# v1_0_3_2026-06-08.net
KiCad netlist of a schematic drawn in EasyEDA Pro
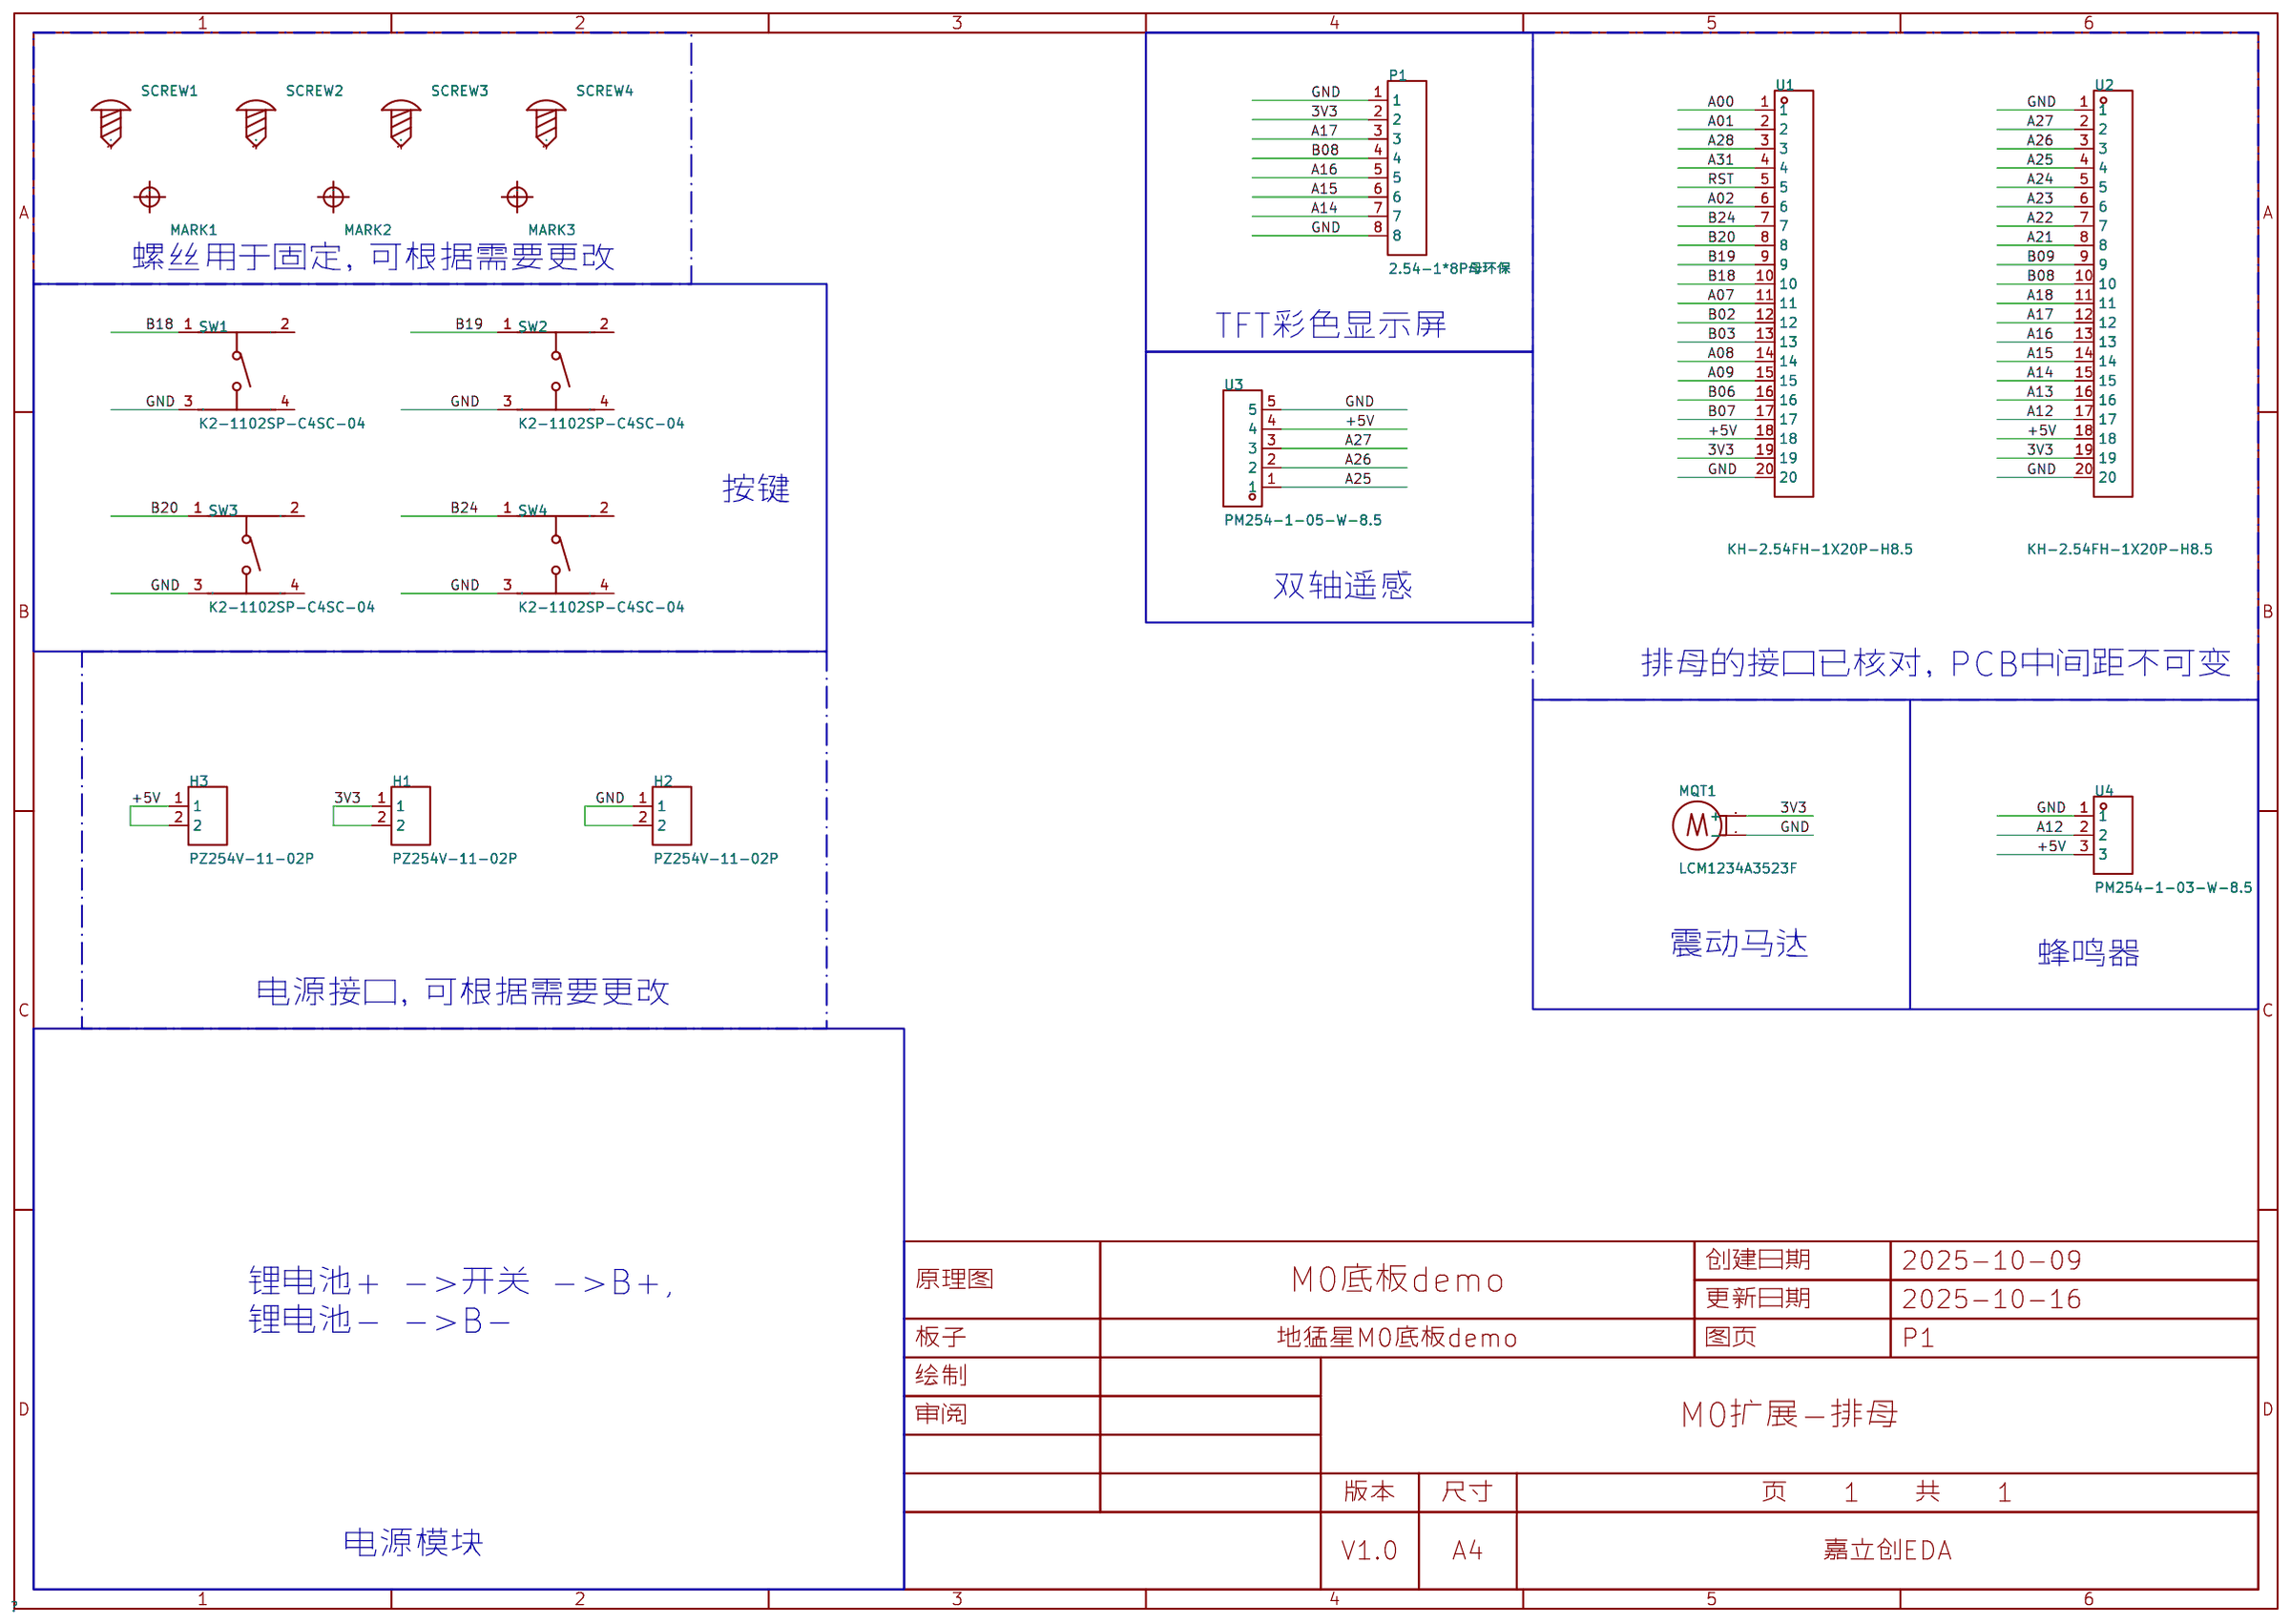
[diagram p0: schematic sheet]

(export (version "E")
  (design (tool "Eeschema 10.0.6"))
  (components
    (comp (ref "H1")
      (value "PZ254V-11-02P")
      (footprint "easyedapro:HDR-TH_2P-P2.54-V-M")
      (fields (field (name "Manufacturer") "XFCN(兴飞)"))
      (libsource (lib "easyedapro") (part "PZ254V-11-02P"))
    )
    (comp (ref "H2")
      (value "PZ254V-11-02P")
      (footprint "easyedapro:HDR-TH_2P-P2.54-V-M")
      (fields (field (name "Manufacturer") "XFCN(兴飞)"))
      (libsource (lib "easyedapro") (part "PZ254V-11-02P"))
    )
    (comp (ref "H3")
      (value "PZ254V-11-02P")
      (footprint "easyedapro:HDR-TH_2P-P2.54-V-M")
      (fields (field (name "Manufacturer") "XFCN(兴飞)"))
      (libsource (lib "easyedapro") (part "PZ254V-11-02P"))
    )
    (comp (ref "MARK1")
      (value "~")
      (footprint "easyedapro:Mark-Point-1mm")
      (libsource (lib "easyedapro") (part "Mark-Point"))
    )
    (comp (ref "MARK2")
      (value "~")
      (footprint "easyedapro:Mark-Point-1mm")
      (libsource (lib "easyedapro") (part "Mark-Point"))
    )
    (comp (ref "MARK3")
      (value "~")
      (footprint "easyedapro:Mark-Point-1mm")
      (libsource (lib "easyedapro") (part "Mark-Point"))
    )
    (comp (ref "MQT1")
      (value "LCM1234A3523F")
      (footprint "easyedapro:VIBRATING-MOTOR-SMD_WELDING")
      (fields (field (name "Manufacturer") "LEADER(立得)"))
      (libsource (lib "easyedapro") (part "LCM1234A3523F"))
    )
    (comp (ref "P1")
      (value "2.54-1*8P母环保")
      (footprint "easyedapro:HDR-TH_8P-P2.54-V-F")
      (fields (field (name "Manufacturer") "BOOMELE(博穆精密)"))
      (libsource (lib "easyedapro") (part "Header-Female-2.54_1x8"))
    )
    (comp (ref "SCREW1")
      (value "~")
      (footprint "easyedapro:M3螺丝")
      (libsource (lib "easyedapro") (part "螺丝孔"))
    )
    (comp (ref "SCREW2")
      (value "~")
      (footprint "easyedapro:M3螺丝")
      (libsource (lib "easyedapro") (part "螺丝孔"))
    )
    (comp (ref "SCREW3")
      (value "~")
      (footprint "easyedapro:M3螺丝")
      (libsource (lib "easyedapro") (part "螺丝孔"))
    )
    (comp (ref "SCREW4")
      (value "~")
      (footprint "easyedapro:M3螺丝")
      (libsource (lib "easyedapro") (part "螺丝孔"))
    )
    (comp (ref "SW1")
      (value "K2-1102SP-C4SC-04")
      (footprint "easyedapro:KEY-SMD_4P-L6.0-W6.0-P4.50-LS9.5-BL")
      (description "电路结构:单刀单掷;按钮形状:圆形按钮;作用力:2.5N;安装方式:立贴;开关长度:6mm;开关宽度:6mm;开关高度:5mm;触点电流:50mA;额定电压:12V;带灯:-;工作寿命:10万次;")
      (fields (field (name "Manufacturer") "韩国韩荣"))
      (libsource (lib "easyedapro") (part "K2-1102SP-C4SC-04"))
    )
    (comp (ref "SW2")
      (value "K2-1102SP-C4SC-04")
      (footprint "easyedapro:KEY-SMD_4P-L6.0-W6.0-P4.50-LS9.5-BL")
      (description "电路结构:单刀单掷;按钮形状:圆形按钮;作用力:2.5N;安装方式:立贴;开关长度:6mm;开关宽度:6mm;开关高度:5mm;触点电流:50mA;额定电压:12V;带灯:-;工作寿命:10万次;")
      (fields (field (name "Manufacturer") "韩国韩荣"))
      (libsource (lib "easyedapro") (part "K2-1102SP-C4SC-04"))
    )
    (comp (ref "SW3")
      (value "K2-1102SP-C4SC-04")
      (footprint "easyedapro:KEY-SMD_4P-L6.0-W6.0-P4.50-LS9.5-BL")
      (description "电路结构:单刀单掷;按钮形状:圆形按钮;作用力:2.5N;安装方式:立贴;开关长度:6mm;开关宽度:6mm;开关高度:5mm;触点电流:50mA;额定电压:12V;带灯:-;工作寿命:10万次;")
      (fields (field (name "Manufacturer") "韩国韩荣"))
      (libsource (lib "easyedapro") (part "K2-1102SP-C4SC-04"))
    )
    (comp (ref "SW4")
      (value "K2-1102SP-C4SC-04")
      (footprint "easyedapro:KEY-SMD_4P-L6.0-W6.0-P4.50-LS9.5-BL")
      (description "电路结构:单刀单掷;按钮形状:圆形按钮;作用力:2.5N;安装方式:立贴;开关长度:6mm;开关宽度:6mm;开关高度:5mm;触点电流:50mA;额定电压:12V;带灯:-;工作寿命:10万次;")
      (fields (field (name "Manufacturer") "韩国韩荣"))
      (libsource (lib "easyedapro") (part "K2-1102SP-C4SC-04"))
    )
    (comp (ref "U1")
      (value "KH-2.54FH-1X20P-H8.5")
      (footprint "easyedapro:HDR-TH_20P-P2.54-V-F-2")
      (fields (field (name "Manufacturer") "kinghelm(金航标)"))
      (libsource (lib "easyedapro") (part "KH-2.54FH-1X20P-H8.5"))
    )
    (comp (ref "U2")
      (value "KH-2.54FH-1X20P-H8.5")
      (footprint "easyedapro:HDR-TH_20P-P2.54-V-F-2")
      (fields (field (name "Manufacturer") "kinghelm(金航标)"))
      (libsource (lib "easyedapro") (part "KH-2.54FH-1X20P-H8.5"))
    )
    (comp (ref "U3")
      (value "PM254-1-05-W-8.5")
      (footprint "easyedapro:HDR-TH_5P-P2.54-H-F-W10.0-N")
      (fields (field (name "Manufacturer") "HCTL(华灿天禄)"))
      (libsource (lib "easyedapro") (part "PM254-1-05-W-8.5"))
    )
    (comp (ref "U4")
      (value "PM254-1-03-W-8.5")
      (footprint "easyedapro:HDR-TH_3P-P2.54-H-F-W10.0-N")
      (fields (field (name "Manufacturer") "HCTL(华灿天禄)"))
      (libsource (lib "easyedapro") (part "PM254-1-03-W-8.5"))
    )
  )
  (nets
    (net (code "1") (name "/+5V") (class "Default")
      (node (ref "H3") (pin "1") (pinfunction "1_1") (pintype "unspecified"))
      (node (ref "H3") (pin "2") (pinfunction "2_2") (pintype "unspecified"))
      (node (ref "U1") (pin "18") (pinfunction "18_18") (pintype "unspecified"))
      (node (ref "U2") (pin "18") (pinfunction "18_18") (pintype "unspecified"))
      (node (ref "U3") (pin "4") (pinfunction "4_4") (pintype "unspecified"))
      (node (ref "U4") (pin "3") (pinfunction "3_3") (pintype "unspecified"))
    )
    (net (code "2") (name "/3V3") (class "Default")
      (node (ref "H1") (pin "1") (pinfunction "1_1") (pintype "unspecified"))
      (node (ref "H1") (pin "2") (pinfunction "2_2") (pintype "unspecified"))
      (node (ref "MQT1") (pin "2") (pinfunction "+_2") (pintype "unspecified"))
      (node (ref "P1") (pin "2") (pinfunction "2_2") (pintype "unspecified"))
      (node (ref "U1") (pin "19") (pinfunction "19_19") (pintype "unspecified"))
      (node (ref "U2") (pin "19") (pinfunction "19_19") (pintype "unspecified"))
    )
    (net (code "3") (name "/A00") (class "Default")
      (node (ref "U1") (pin "1") (pinfunction "1_1") (pintype "unspecified"))
    )
    (net (code "4") (name "/A01") (class "Default")
      (node (ref "U1") (pin "2") (pinfunction "2_2") (pintype "unspecified"))
    )
    (net (code "5") (name "/A02") (class "Default")
      (node (ref "U1") (pin "6") (pinfunction "6_6") (pintype "unspecified"))
    )
    (net (code "6") (name "/A07") (class "Default")
      (node (ref "U1") (pin "11") (pinfunction "11_11") (pintype "unspecified"))
    )
    (net (code "7") (name "/A08") (class "Default")
      (node (ref "U1") (pin "14") (pinfunction "14_14") (pintype "unspecified"))
    )
    (net (code "8") (name "/A09") (class "Default")
      (node (ref "U1") (pin "15") (pinfunction "15_15") (pintype "unspecified"))
    )
    (net (code "9") (name "/A12") (class "Default")
      (node (ref "U2") (pin "17") (pinfunction "17_17") (pintype "unspecified"))
      (node (ref "U4") (pin "2") (pinfunction "2_2") (pintype "unspecified"))
    )
    (net (code "10") (name "/A13") (class "Default")
      (node (ref "U2") (pin "16") (pinfunction "16_16") (pintype "unspecified"))
    )
    (net (code "11") (name "/A14") (class "Default")
      (node (ref "P1") (pin "7") (pinfunction "7_7") (pintype "unspecified"))
      (node (ref "U2") (pin "15") (pinfunction "15_15") (pintype "unspecified"))
    )
    (net (code "12") (name "/A15") (class "Default")
      (node (ref "P1") (pin "6") (pinfunction "6_6") (pintype "unspecified"))
      (node (ref "U2") (pin "14") (pinfunction "14_14") (pintype "unspecified"))
    )
    (net (code "13") (name "/A16") (class "Default")
      (node (ref "P1") (pin "5") (pinfunction "5_5") (pintype "unspecified"))
      (node (ref "U2") (pin "13") (pinfunction "13_13") (pintype "unspecified"))
    )
    (net (code "14") (name "/A17") (class "Default")
      (node (ref "P1") (pin "3") (pinfunction "3_3") (pintype "unspecified"))
      (node (ref "U2") (pin "12") (pinfunction "12_12") (pintype "unspecified"))
    )
    (net (code "15") (name "/A18") (class "Default")
      (node (ref "U2") (pin "11") (pinfunction "11_11") (pintype "unspecified"))
    )
    (net (code "16") (name "/A21") (class "Default")
      (node (ref "U2") (pin "8") (pinfunction "8_8") (pintype "unspecified"))
    )
    (net (code "17") (name "/A22") (class "Default")
      (node (ref "U2") (pin "7") (pinfunction "7_7") (pintype "unspecified"))
    )
    (net (code "18") (name "/A23") (class "Default")
      (node (ref "U2") (pin "6") (pinfunction "6_6") (pintype "unspecified"))
    )
    (net (code "19") (name "/A24") (class "Default")
      (node (ref "U2") (pin "5") (pinfunction "5_5") (pintype "unspecified"))
    )
    (net (code "20") (name "/A25") (class "Default")
      (node (ref "U2") (pin "4") (pinfunction "4_4") (pintype "unspecified"))
      (node (ref "U3") (pin "1") (pinfunction "1_1") (pintype "unspecified"))
    )
    (net (code "21") (name "/A26") (class "Default")
      (node (ref "U2") (pin "3") (pinfunction "3_3") (pintype "unspecified"))
      (node (ref "U3") (pin "2") (pinfunction "2_2") (pintype "unspecified"))
    )
    (net (code "22") (name "/A27") (class "Default")
      (node (ref "U2") (pin "2") (pinfunction "2_2") (pintype "unspecified"))
      (node (ref "U3") (pin "3") (pinfunction "3_3") (pintype "unspecified"))
    )
    (net (code "23") (name "/A28") (class "Default")
      (node (ref "U1") (pin "3") (pinfunction "3_3") (pintype "unspecified"))
    )
    (net (code "24") (name "/A31") (class "Default")
      (node (ref "U1") (pin "4") (pinfunction "4_4") (pintype "unspecified"))
    )
    (net (code "25") (name "/B02") (class "Default")
      (node (ref "U1") (pin "12") (pinfunction "12_12") (pintype "unspecified"))
    )
    (net (code "26") (name "/B03") (class "Default")
      (node (ref "U1") (pin "13") (pinfunction "13_13") (pintype "unspecified"))
    )
    (net (code "27") (name "/B06") (class "Default")
      (node (ref "U1") (pin "16") (pinfunction "16_16") (pintype "unspecified"))
    )
    (net (code "28") (name "/B07") (class "Default")
      (node (ref "U1") (pin "17") (pinfunction "17_17") (pintype "unspecified"))
    )
    (net (code "29") (name "/B08") (class "Default")
      (node (ref "P1") (pin "4") (pinfunction "4_4") (pintype "unspecified"))
      (node (ref "U2") (pin "10") (pinfunction "10_10") (pintype "unspecified"))
    )
    (net (code "30") (name "/B09") (class "Default")
      (node (ref "U2") (pin "9") (pinfunction "9_9") (pintype "unspecified"))
    )
    (net (code "31") (name "/B18") (class "Default")
      (node (ref "SW1") (pin "1") (pinfunction "1_1") (pintype "unspecified"))
      (node (ref "U1") (pin "10") (pinfunction "10_10") (pintype "unspecified"))
    )
    (net (code "32") (name "/B19") (class "Default")
      (node (ref "SW2") (pin "1") (pinfunction "1_1") (pintype "unspecified"))
      (node (ref "U1") (pin "9") (pinfunction "9_9") (pintype "unspecified"))
    )
    (net (code "33") (name "/B20") (class "Default")
      (node (ref "SW3") (pin "1") (pinfunction "1_1") (pintype "unspecified"))
      (node (ref "U1") (pin "8") (pinfunction "8_8") (pintype "unspecified"))
    )
    (net (code "34") (name "/B24") (class "Default")
      (node (ref "SW4") (pin "1") (pinfunction "1_1") (pintype "unspecified"))
      (node (ref "U1") (pin "7") (pinfunction "7_7") (pintype "unspecified"))
    )
    (net (code "35") (name "/GND") (class "Default")
      (node (ref "H2") (pin "1") (pinfunction "1_1") (pintype "unspecified"))
      (node (ref "H2") (pin "2") (pinfunction "2_2") (pintype "unspecified"))
      (node (ref "MQT1") (pin "1") (pinfunction "-_1") (pintype "unspecified"))
      (node (ref "P1") (pin "1") (pinfunction "1_1") (pintype "unspecified"))
      (node (ref "P1") (pin "8") (pinfunction "8_8") (pintype "unspecified"))
      (node (ref "SW1") (pin "3") (pinfunction "3_3") (pintype "unspecified"))
      (node (ref "SW2") (pin "3") (pinfunction "3_3") (pintype "unspecified"))
      (node (ref "SW3") (pin "3") (pinfunction "3_3") (pintype "unspecified"))
      (node (ref "SW4") (pin "3") (pinfunction "3_3") (pintype "unspecified"))
      (node (ref "U1") (pin "20") (pinfunction "20_20") (pintype "unspecified"))
      (node (ref "U2") (pin "1") (pinfunction "1_1") (pintype "unspecified"))
      (node (ref "U2") (pin "20") (pinfunction "20_20") (pintype "unspecified"))
      (node (ref "U3") (pin "5") (pinfunction "5_5") (pintype "unspecified"))
      (node (ref "U4") (pin "1") (pinfunction "1_1") (pintype "unspecified"))
    )
    (net (code "36") (name "/RST") (class "Default")
      (node (ref "U1") (pin "5") (pinfunction "5_5") (pintype "unspecified"))
    )
    (net (code "37") (name "unconnected-(MARK1-Pad1)") (class "Default")
      (node (ref "MARK1") (pin "1") (pinfunction "1_1") (pintype "input"))
    )
    (net (code "38") (name "unconnected-(MARK2-Pad1)") (class "Default")
      (node (ref "MARK2") (pin "1") (pinfunction "1_1") (pintype "input"))
    )
    (net (code "39") (name "unconnected-(MARK3-Pad1)") (class "Default")
      (node (ref "MARK3") (pin "1") (pinfunction "1_1") (pintype "input"))
    )
    (net (code "40") (name "unconnected-(SCREW1-Pad1)") (class "Default")
      (node (ref "SCREW1") (pin "1") (pinfunction "1_1") (pintype "input"))
    )
    (net (code "41") (name "unconnected-(SCREW2-Pad1)") (class "Default")
      (node (ref "SCREW2") (pin "1") (pinfunction "1_1") (pintype "input"))
    )
    (net (code "42") (name "unconnected-(SCREW3-Pad1)") (class "Default")
      (node (ref "SCREW3") (pin "1") (pinfunction "1_1") (pintype "input"))
    )
    (net (code "43") (name "unconnected-(SCREW4-Pad1)") (class "Default")
      (node (ref "SCREW4") (pin "1") (pinfunction "1_1") (pintype "input"))
    )
    (net (code "44") (name "unconnected-(SW1-Pad2)") (class "Default")
      (node (ref "SW1") (pin "2") (pinfunction "2_2") (pintype "unspecified"))
    )
    (net (code "45") (name "unconnected-(SW1-Pad4)") (class "Default")
      (node (ref "SW1") (pin "4") (pinfunction "4_4") (pintype "unspecified"))
    )
    (net (code "46") (name "unconnected-(SW2-Pad2)") (class "Default")
      (node (ref "SW2") (pin "2") (pinfunction "2_2") (pintype "unspecified"))
    )
    (net (code "47") (name "unconnected-(SW2-Pad4)") (class "Default")
      (node (ref "SW2") (pin "4") (pinfunction "4_4") (pintype "unspecified"))
    )
    (net (code "48") (name "unconnected-(SW3-Pad2)") (class "Default")
      (node (ref "SW3") (pin "2") (pinfunction "2_2") (pintype "unspecified"))
    )
    (net (code "49") (name "unconnected-(SW3-Pad4)") (class "Default")
      (node (ref "SW3") (pin "4") (pinfunction "4_4") (pintype "unspecified"))
    )
    (net (code "50") (name "unconnected-(SW4-Pad2)") (class "Default")
      (node (ref "SW4") (pin "2") (pinfunction "2_2") (pintype "unspecified"))
    )
    (net (code "51") (name "unconnected-(SW4-Pad4)") (class "Default")
      (node (ref "SW4") (pin "4") (pinfunction "4_4") (pintype "unspecified"))
    )
  )
)
